# Celda_interna.net
KiCad netlist of a schematic drawn in EAGLE
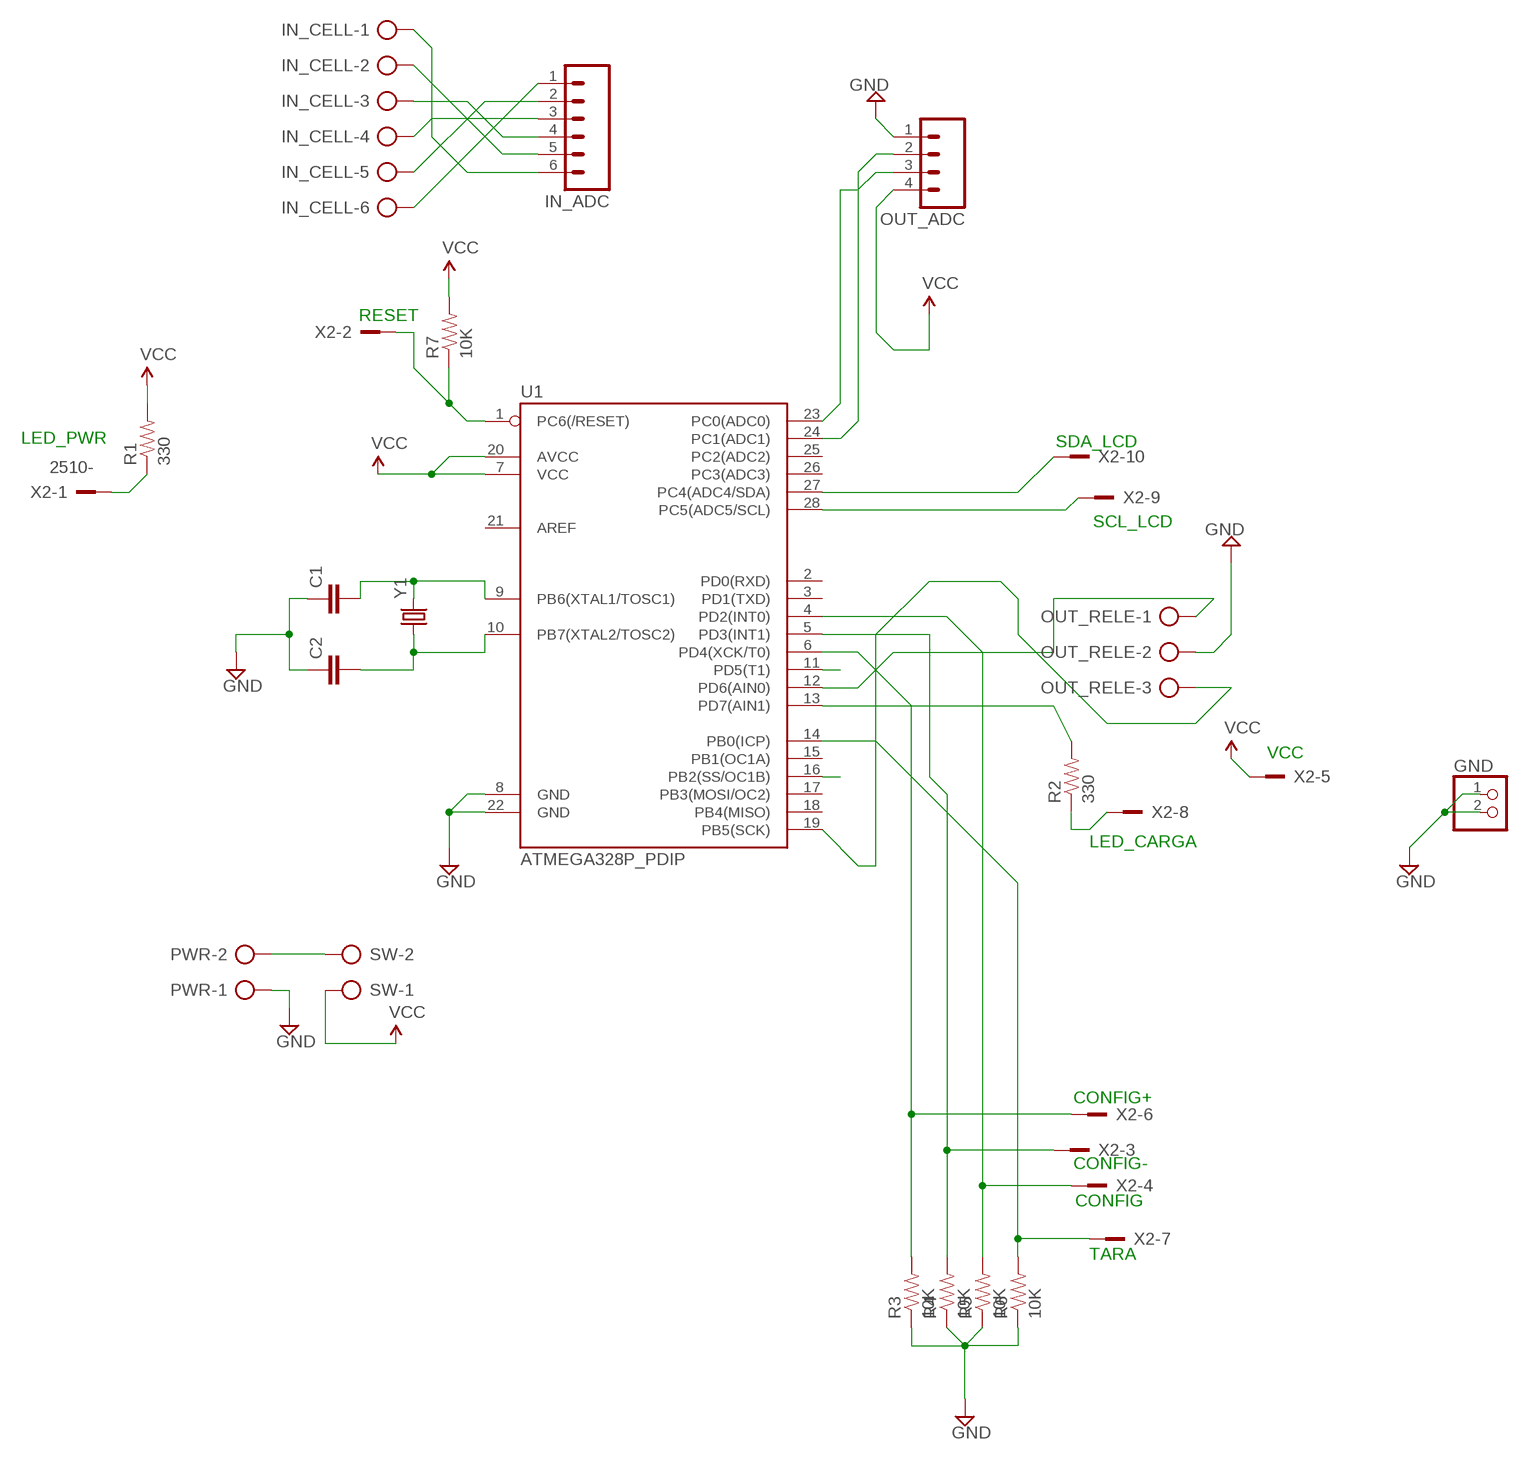
[diagram p0: schematic, sheet 1]

(export (version "E")
  (design (tool "Eeschema 10.0.6"))
  (components
    (comp (ref "C1")
      (value "CAPKIT")
      (footprint "eagle-import:CAP-PTH-SMALL-KIT")
      (libsource (lib "eagle-import") (part "CAPKIT"))
    )
    (comp (ref "C2")
      (value "CAPKIT")
      (footprint "eagle-import:CAP-PTH-SMALL-KIT")
      (libsource (lib "eagle-import") (part "CAPKIT"))
    )
    (comp (ref "GND")
      (value "PINHD-1X2")
      (footprint "eagle-import:1X02")
      (libsource (lib "eagle-import") (part "PINHD-1X2"))
    )
    (comp (ref "IN_ADC")
      (value "M06LONGPADS")
      (footprint "eagle-import:1X06_LONGPADS")
      (libsource (lib "eagle-import") (part "M06LONGPADS"))
    )
    (comp (ref "IN_CELL")
      (value "AK500/6")
      (footprint "eagle-import:AK500_6")
      (libsource (lib "eagle-import") (part "AK500/6"))
    )
    (comp (ref "OUT_ADC")
      (value "M04LONGPADS")
      (footprint "eagle-import:1X04_LONGPADS")
      (libsource (lib "eagle-import") (part "M04LONGPADS"))
    )
    (comp (ref "OUT_RELE")
      (value "AK500/3")
      (footprint "eagle-import:AK500_3")
      (libsource (lib "eagle-import") (part "AK500/3"))
    )
    (comp (ref "PWR")
      (value "AK500/2")
      (footprint "eagle-import:AK500_2")
      (libsource (lib "eagle-import") (part "AK500/2"))
    )
    (comp (ref "R1")
      (value "330")
      (footprint "eagle-import:AXIAL-0.4")
      (libsource (lib "eagle-import") (part "RESISTORPTH-1/4W"))
    )
    (comp (ref "R2")
      (value "330")
      (footprint "eagle-import:AXIAL-0.4")
      (libsource (lib "eagle-import") (part "RESISTORPTH-1/4W"))
    )
    (comp (ref "R3")
      (value "10K")
      (footprint "eagle-import:AXIAL-0.4")
      (libsource (lib "eagle-import") (part "RESISTORPTH-1/4W"))
    )
    (comp (ref "R4")
      (value "10K")
      (footprint "eagle-import:AXIAL-0.4")
      (libsource (lib "eagle-import") (part "RESISTORPTH-1/4W"))
    )
    (comp (ref "R5")
      (value "10K")
      (footprint "eagle-import:AXIAL-0.4")
      (libsource (lib "eagle-import") (part "RESISTORPTH-1/4W"))
    )
    (comp (ref "R6")
      (value "10K")
      (footprint "eagle-import:AXIAL-0.4")
      (libsource (lib "eagle-import") (part "RESISTORPTH-1/4W"))
    )
    (comp (ref "R7")
      (value "10K")
      (footprint "eagle-import:AXIAL-0.4")
      (libsource (lib "eagle-import") (part "RESISTORPTH-1/4W"))
    )
    (comp (ref "SW")
      (value "AK500/2")
      (footprint "eagle-import:AK500_2")
      (libsource (lib "eagle-import") (part "AK500/2"))
    )
    (comp (ref "U1")
      (value "ATMEGA328P_PDIP")
      (footprint "eagle-import:DIL28-3")
      (libsource (lib "eagle-import") (part "ATMEGA328P_PDIP"))
    )
    (comp (ref "X2")
      (value "2510-")
      (footprint "eagle-import:PAK100_2500-10")
      (fields (field (name "MF") "3M") (field (name "MPN") "2510-6002UB"))
      (libsource (lib "eagle-import") (part "2510-"))
    )
    (comp (ref "Y1")
      (value "CRYSTALHC49US")
      (footprint "eagle-import:HC49US")
      (libsource (lib "eagle-import") (part "CRYSTALHC49US"))
    )
  )
  (nets
    (net (code "1") (name "GND") (class "Default")
      (node (ref "C1") (pin "1") (pinfunction "1_1") (pintype "passive"))
      (node (ref "C2") (pin "1") (pinfunction "1_1") (pintype "passive"))
      (node (ref "GND") (pin "1") (pinfunction "1_1") (pintype "passive"))
      (node (ref "GND") (pin "2") (pinfunction "2_2") (pintype "passive"))
      (node (ref "OUT_ADC") (pin "1") (pinfunction "1_1") (pintype "passive"))
      (node (ref "OUT_RELE") (pin "2") (pinfunction "KL_2") (pintype "passive"))
      (node (ref "PWR") (pin "1") (pinfunction "KL_1") (pintype "passive"))
      (node (ref "R3") (pin "P$1") (pinfunction "1_P$1") (pintype "passive"))
      (node (ref "R4") (pin "P$1") (pinfunction "1_P$1") (pintype "passive"))
      (node (ref "R5") (pin "P$1") (pinfunction "1_P$1") (pintype "passive"))
      (node (ref "R6") (pin "P$1") (pinfunction "1_P$1") (pintype "passive"))
      (node (ref "U1") (pin "22") (pinfunction "GND_22") (pintype "bidirectional"))
      (node (ref "U1") (pin "8") (pinfunction "GND_8") (pintype "bidirectional"))
    )
    (net (code "2") (name "Net-(IN_CELLA-KL)") (class "Default")
      (node (ref "IN_ADC") (pin "6") (pinfunction "6_6") (pintype "passive"))
      (node (ref "IN_CELL") (pin "1") (pinfunction "KL_1") (pintype "passive"))
    )
    (net (code "3") (name "Net-(IN_CELLB-KL)") (class "Default")
      (node (ref "IN_ADC") (pin "5") (pinfunction "5_5") (pintype "passive"))
      (node (ref "IN_CELL") (pin "2") (pinfunction "KL_2") (pintype "passive"))
    )
    (net (code "4") (name "Net-(IN_CELLC-KL)") (class "Default")
      (node (ref "IN_ADC") (pin "4") (pinfunction "4_4") (pintype "passive"))
      (node (ref "IN_CELL") (pin "3") (pinfunction "KL_3") (pintype "passive"))
    )
    (net (code "5") (name "Net-(IN_CELLD-KL)") (class "Default")
      (node (ref "IN_ADC") (pin "3") (pinfunction "3_3") (pintype "passive"))
      (node (ref "IN_CELL") (pin "4") (pinfunction "KL_4") (pintype "passive"))
    )
    (net (code "6") (name "Net-(IN_CELLE-KL)") (class "Default")
      (node (ref "IN_ADC") (pin "2") (pinfunction "2_2") (pintype "passive"))
      (node (ref "IN_CELL") (pin "5") (pinfunction "KL_5") (pintype "passive"))
    )
    (net (code "7") (name "Net-(IN_CELLF-KL)") (class "Default")
      (node (ref "IN_ADC") (pin "1") (pinfunction "1_1") (pintype "passive"))
      (node (ref "IN_CELL") (pin "6") (pinfunction "KL_6") (pintype "passive"))
    )
    (net (code "8") (name "Net-(OUT_RELEA-KL)") (class "Default")
      (node (ref "OUT_RELE") (pin "1") (pinfunction "KL_1") (pintype "passive"))
      (node (ref "U1") (pin "12") (pinfunction "PD6(AIN0)_12") (pintype "bidirectional"))
    )
    (net (code "9") (name "Net-(OUT_RELEC-KL)") (class "Default")
      (node (ref "OUT_RELE") (pin "3") (pinfunction "KL_3") (pintype "passive"))
      (node (ref "U1") (pin "19") (pinfunction "PB5(SCK)_19") (pintype "bidirectional"))
    )
    (net (code "10") (name "Net-(PWRB-KL)") (class "Default")
      (node (ref "PWR") (pin "2") (pinfunction "KL_2") (pintype "passive"))
      (node (ref "SW") (pin "2") (pinfunction "KL_2") (pintype "passive"))
    )
    (net (code "11") (name "Net-(R1-1)") (class "Default")
      (node (ref "R1") (pin "P$1") (pinfunction "1_P$1") (pintype "passive"))
      (node (ref "X2") (pin "1") (pinfunction "KL_1") (pintype "passive"))
    )
    (net (code "12") (name "Net-(R2-1)") (class "Default")
      (node (ref "R2") (pin "P$1") (pinfunction "1_P$1") (pintype "passive"))
      (node (ref "X2") (pin "8") (pinfunction "KL_8") (pintype "passive"))
    )
    (net (code "13") (name "Net-(R2-2)") (class "Default")
      (node (ref "R2") (pin "P$2") (pinfunction "2_P$2") (pintype "passive"))
      (node (ref "U1") (pin "13") (pinfunction "PD7(AIN1)_13") (pintype "bidirectional"))
    )
    (net (code "14") (name "Net-(R3-2)") (class "Default")
      (node (ref "R3") (pin "P$2") (pinfunction "2_P$2") (pintype "passive"))
      (node (ref "U1") (pin "6") (pinfunction "PD4(XCK/T0)_6") (pintype "bidirectional"))
      (node (ref "X2") (pin "6") (pinfunction "KL_6") (pintype "passive"))
    )
    (net (code "15") (name "Net-(R4-2)") (class "Default")
      (node (ref "R4") (pin "P$2") (pinfunction "2_P$2") (pintype "passive"))
      (node (ref "U1") (pin "5") (pinfunction "PD3(INT1)_5") (pintype "bidirectional"))
      (node (ref "X2") (pin "3") (pinfunction "KL_3") (pintype "passive"))
    )
    (net (code "16") (name "Net-(R5-2)") (class "Default")
      (node (ref "R5") (pin "P$2") (pinfunction "2_P$2") (pintype "passive"))
      (node (ref "U1") (pin "4") (pinfunction "PD2(INT0)_4") (pintype "bidirectional"))
      (node (ref "X2") (pin "4") (pinfunction "KL_4") (pintype "passive"))
    )
    (net (code "17") (name "Net-(R6-2)") (class "Default")
      (node (ref "R6") (pin "P$2") (pinfunction "2_P$2") (pintype "passive"))
      (node (ref "U1") (pin "14") (pinfunction "PB0(ICP)_14") (pintype "bidirectional"))
      (node (ref "X2") (pin "7") (pinfunction "KL_7") (pintype "passive"))
    )
    (net (code "18") (name "Net-(R7-1)") (class "Default")
      (node (ref "R7") (pin "P$1") (pinfunction "1_P$1") (pintype "passive"))
      (node (ref "U1") (pin "1") (pinfunction "PC6(/RESET)_1") (pintype "bidirectional"))
      (node (ref "X2") (pin "2") (pinfunction "KL_2") (pintype "passive"))
    )
    (net (code "19") (name "Net-(U1-PB6(XTAL1{slash}TOSC1))") (class "Default")
      (node (ref "C1") (pin "2") (pinfunction "2_2") (pintype "passive"))
      (node (ref "U1") (pin "9") (pinfunction "PB6(XTAL1/TOSC1)_9") (pintype "bidirectional"))
      (node (ref "Y1") (pin "2") (pinfunction "2_2") (pintype "passive"))
    )
    (net (code "20") (name "Net-(U1-PB7(XTAL2{slash}TOSC2))") (class "Default")
      (node (ref "C2") (pin "2") (pinfunction "2_2") (pintype "passive"))
      (node (ref "U1") (pin "10") (pinfunction "PB7(XTAL2/TOSC2)_10") (pintype "bidirectional"))
      (node (ref "Y1") (pin "1") (pinfunction "1_1") (pintype "passive"))
    )
    (net (code "21") (name "Net-(U1-PC0(ADC0))") (class "Default")
      (node (ref "OUT_ADC") (pin "3") (pinfunction "3_3") (pintype "passive"))
      (node (ref "U1") (pin "23") (pinfunction "PC0(ADC0)_23") (pintype "bidirectional"))
    )
    (net (code "22") (name "Net-(U1-PC1(ADC1))") (class "Default")
      (node (ref "OUT_ADC") (pin "2") (pinfunction "2_2") (pintype "passive"))
      (node (ref "U1") (pin "24") (pinfunction "PC1(ADC1)_24") (pintype "bidirectional"))
    )
    (net (code "23") (name "Net-(U1-PC4(ADC4{slash}SDA))") (class "Default")
      (node (ref "U1") (pin "27") (pinfunction "PC4(ADC4/SDA)_27") (pintype "bidirectional"))
      (node (ref "X2") (pin "10") (pinfunction "KL_10") (pintype "passive"))
    )
    (net (code "24") (name "Net-(U1-PC5(ADC5{slash}SCL))") (class "Default")
      (node (ref "U1") (pin "28") (pinfunction "PC5(ADC5/SCL)_28") (pintype "bidirectional"))
      (node (ref "X2") (pin "9") (pinfunction "KL_9") (pintype "passive"))
    )
    (net (code "25") (name "VCC") (class "Default")
      (node (ref "OUT_ADC") (pin "4") (pinfunction "4_4") (pintype "passive"))
      (node (ref "R1") (pin "P$2") (pinfunction "2_P$2") (pintype "passive"))
      (node (ref "R7") (pin "P$2") (pinfunction "2_P$2") (pintype "passive"))
      (node (ref "SW") (pin "1") (pinfunction "KL_1") (pintype "passive"))
      (node (ref "U1") (pin "20") (pinfunction "AVCC_20") (pintype "bidirectional"))
      (node (ref "U1") (pin "7") (pinfunction "VCC_7") (pintype "bidirectional"))
      (node (ref "X2") (pin "5") (pinfunction "KL_5") (pintype "passive"))
    )
    (net (code "26") (name "unconnected-(U1-AREF-Pad21)") (class "Default")
      (node (ref "U1") (pin "21") (pinfunction "AREF_21") (pintype "bidirectional"))
    )
    (net (code "27") (name "unconnected-(U1-PB1(OC1A)-Pad15)") (class "Default")
      (node (ref "U1") (pin "15") (pinfunction "PB1(OC1A)_15") (pintype "bidirectional"))
    )
    (net (code "28") (name "unconnected-(U1-PB2(SS{slash}OC1B)-Pad16)") (class "Default")
      (node (ref "U1") (pin "16") (pinfunction "PB2(SS/OC1B)_16") (pintype "bidirectional"))
    )
    (net (code "29") (name "unconnected-(U1-PB3(MOSI{slash}OC2)-Pad17)") (class "Default")
      (node (ref "U1") (pin "17") (pinfunction "PB3(MOSI/OC2)_17") (pintype "bidirectional"))
    )
    (net (code "30") (name "unconnected-(U1-PB4(MISO)-Pad18)") (class "Default")
      (node (ref "U1") (pin "18") (pinfunction "PB4(MISO)_18") (pintype "bidirectional"))
    )
    (net (code "31") (name "unconnected-(U1-PC2(ADC2)-Pad25)") (class "Default")
      (node (ref "U1") (pin "25") (pinfunction "PC2(ADC2)_25") (pintype "bidirectional"))
    )
    (net (code "32") (name "unconnected-(U1-PC3(ADC3)-Pad26)") (class "Default")
      (node (ref "U1") (pin "26") (pinfunction "PC3(ADC3)_26") (pintype "bidirectional"))
    )
    (net (code "33") (name "unconnected-(U1-PD0(RXD)-Pad2)") (class "Default")
      (node (ref "U1") (pin "2") (pinfunction "PD0(RXD)_2") (pintype "bidirectional"))
    )
    (net (code "34") (name "unconnected-(U1-PD1(TXD)-Pad3)") (class "Default")
      (node (ref "U1") (pin "3") (pinfunction "PD1(TXD)_3") (pintype "bidirectional"))
    )
    (net (code "35") (name "unconnected-(U1-PD5(T1)-Pad11)") (class "Default")
      (node (ref "U1") (pin "11") (pinfunction "PD5(T1)_11") (pintype "bidirectional"))
    )
  )
)
